# SCH_TEST_2022-02-16.net
KiCad netlist of a schematic drawn in EasyEDA
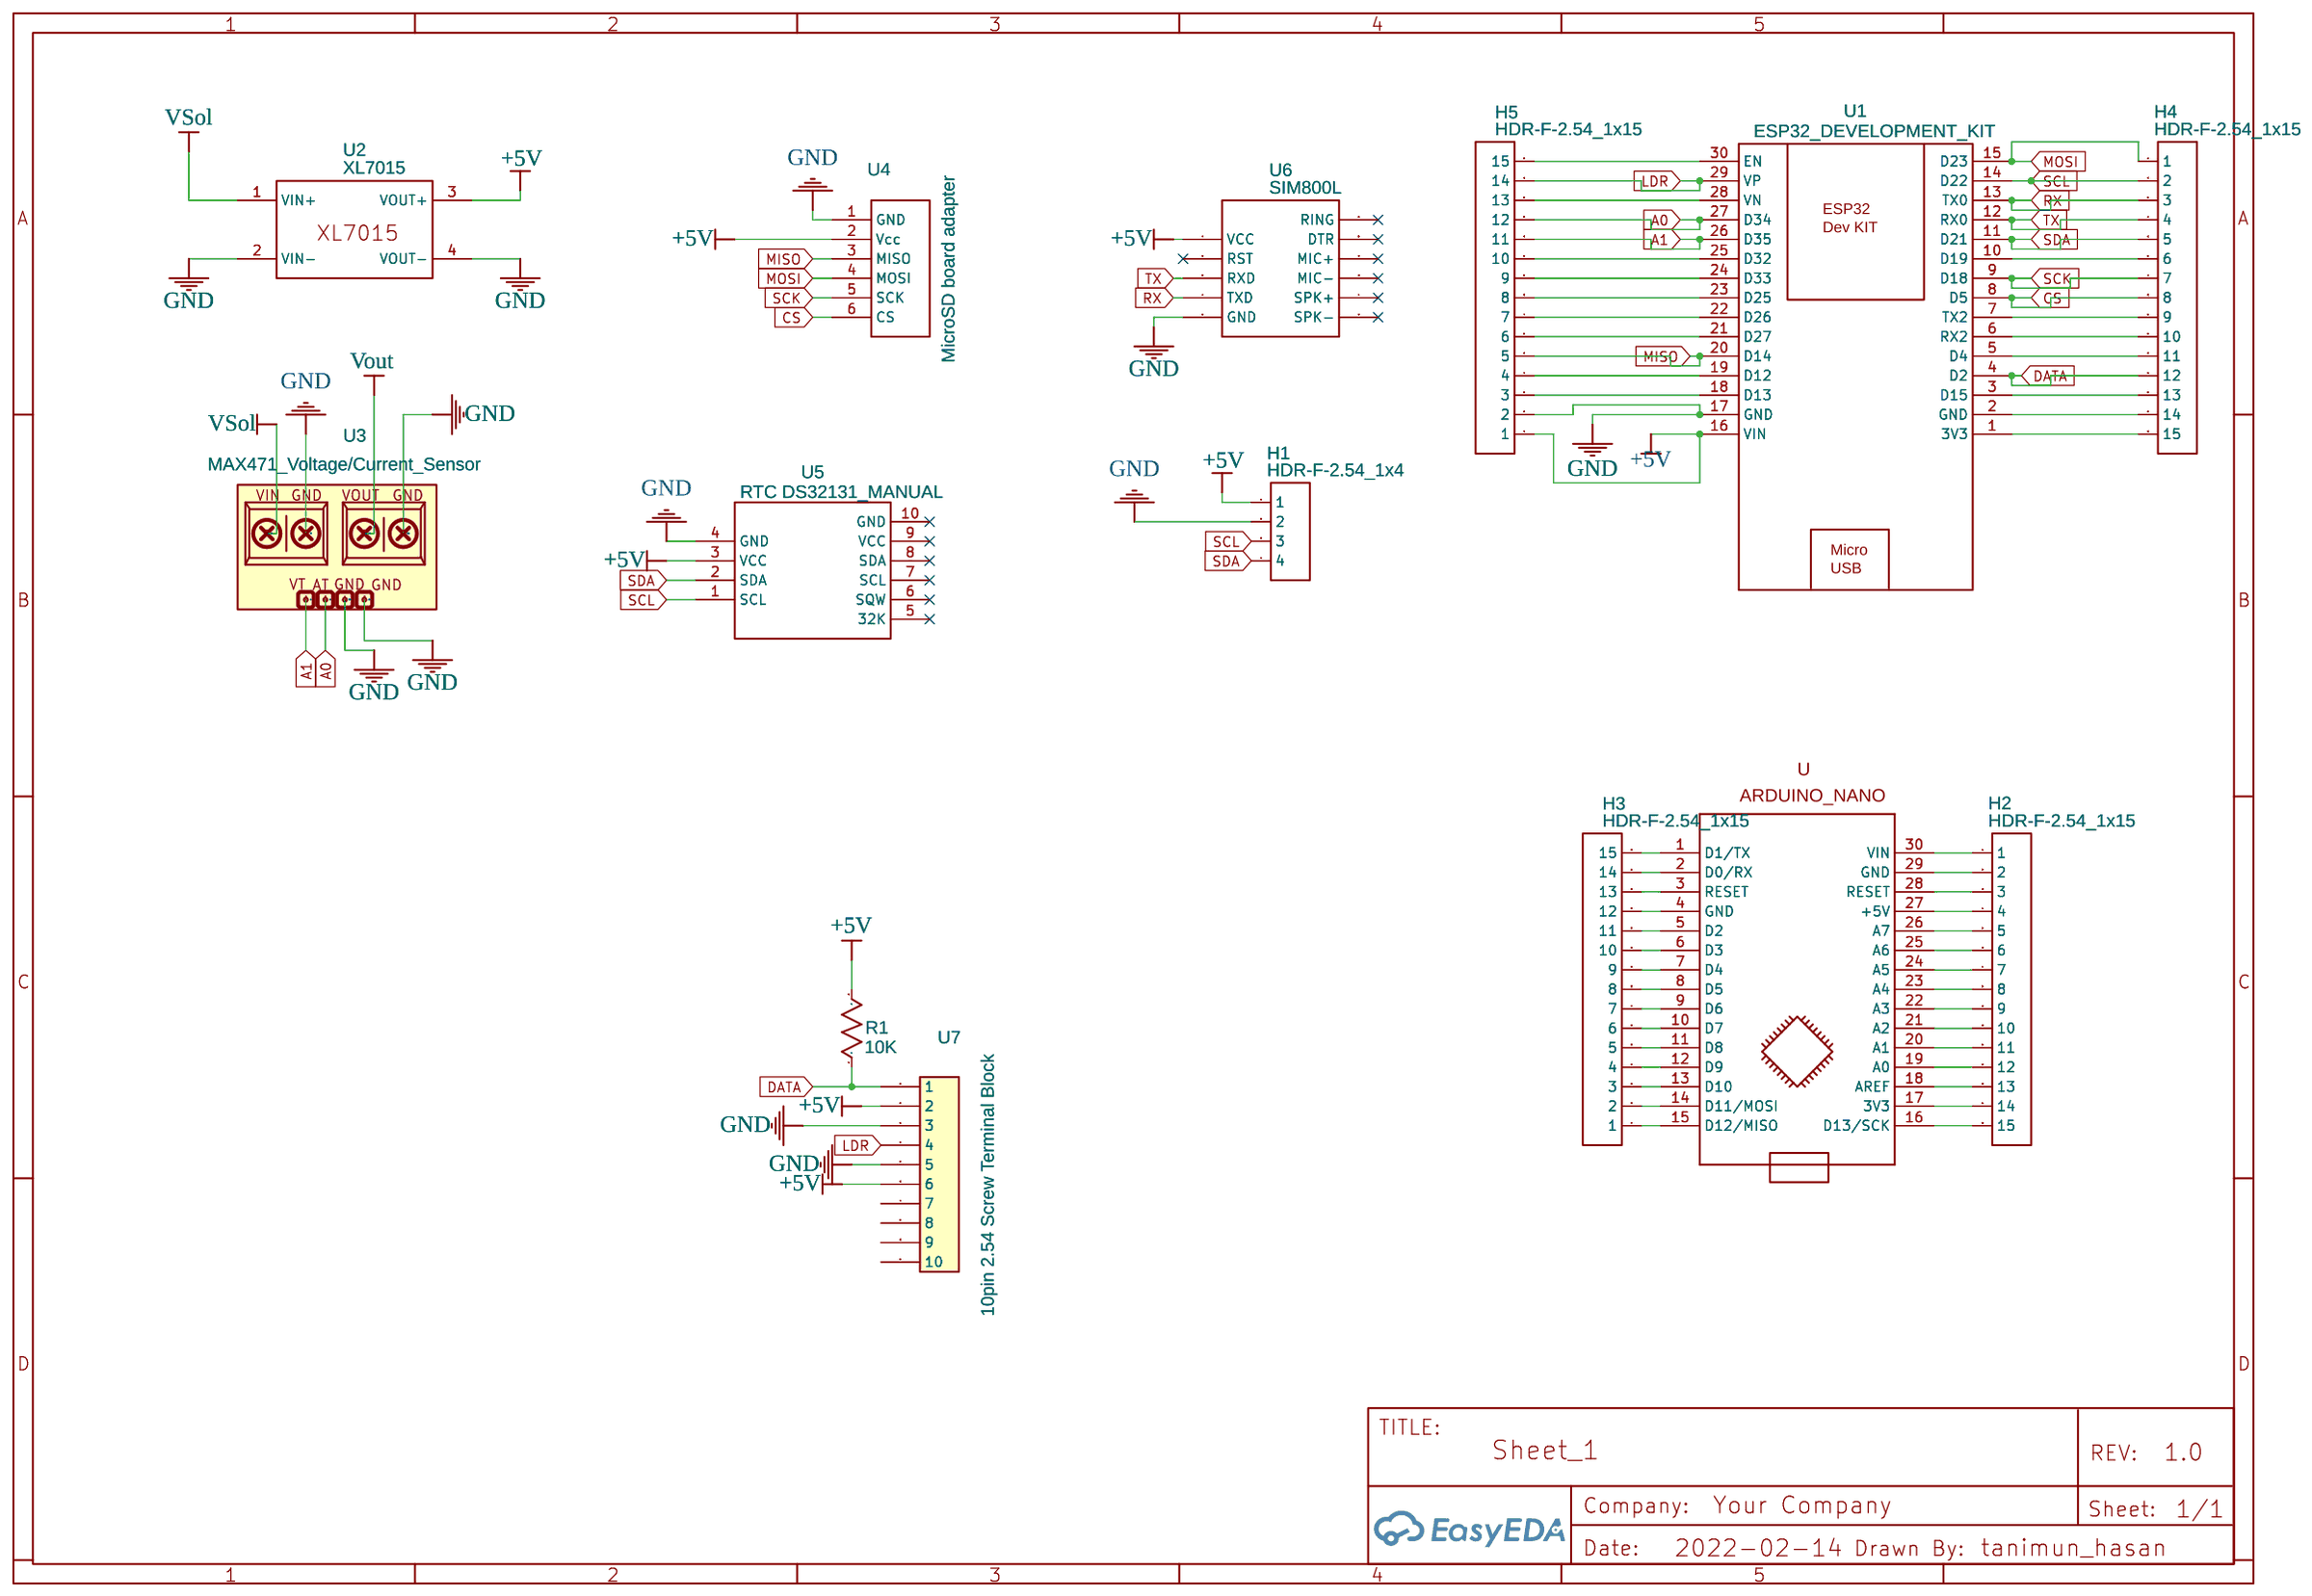
[diagram p0: schematic sheet]

(export (version "E")
  (design (tool "Eeschema 10.0.6"))
  (components
    (comp (ref "H1")
      (value "HDR-F-2.54_1x4")
      (fields (field (name "BOM_Supplier Part") "C225501"))
      (libsource (lib "") (part "HDR-F-2.54_1x4"))
    )
    (comp (ref "H2")
      (value "HDR-F-2.54_1x15")
      (fields (field (name "BOM_Supplier Part") "C124408"))
      (libsource (lib "") (part "HDR-F-2.54_1x15_1"))
    )
    (comp (ref "H3")
      (value "HDR-F-2.54_1x15")
      (fields (field (name "BOM_Supplier Part") "C124408"))
      (libsource (lib "") (part "HDR-F-2.54_1x15"))
    )
    (comp (ref "H4")
      (value "HDR-F-2.54_1x15")
      (fields (field (name "BOM_Supplier Part") "C124408"))
      (libsource (lib "") (part "HDR-F-2.54_1x15_1"))
    )
    (comp (ref "H5")
      (value "HDR-F-2.54_1x15")
      (fields (field (name "BOM_Supplier Part") "C124408"))
      (libsource (lib "") (part "HDR-F-2.54_1x15"))
    )
    (comp (ref "R1") (value "10K") (libsource (lib "") (part "R_AXIAL-0.4_US")))
    (comp (ref "U1")
      (value "ESP32_DEVELOPMENT_KIT")
      (fields (field (name "BOM_Manufacturer Part") "ESP32 Development KIT"))
      (libsource (lib "") (part "ESP32_DEVELOPMENT_KIT"))
    )
    (comp (ref "U2") (value "XL7015") (libsource (lib "") (part "XL7015")))
    (comp (ref "U3")
      (value "MAX471_Voltage/Current_Sensor")
      (libsource (lib "") (part "MAX471_Voltage/Current_Sensor"))
    )
    (comp (ref "U4") (value "MicroSD board adapter") (libsource (lib "") (part "MicroSD board adapter")))
    (comp (ref "U5") (value "RTC DS32131_MANUAL") (libsource (lib "") (part "RTC DS32131_MANUAL")))
    (comp (ref "U6") (value "SIM800L") (libsource (lib "") (part "SIM800L")))
    (comp (ref "U7")
      (value "10pin 2.54 Screw Terminal Block")
      (libsource (lib "") (part "10pin 2.54 Screw Terminal Block"))
    )
    (comp (ref "U8")
      (value "Arduino-NANO")
      (fields (field (name "BOM_Supplier Part") "undefined"))
      (libsource (lib "") (part "Arduino-NANO"))
    )
  )
  (nets
    (net (code "1") (name "+5V") (class "Default")
      (node (ref "H1") (pin "1") (pinfunction "1_1") (pintype "unspecified"))
      (node (ref "H5") (pin "1") (pinfunction "1_1") (pintype "unspecified"))
      (node (ref "R1") (pin "2") (pinfunction "2_2") (pintype "unspecified"))
      (node (ref "U1") (pin "16") (pinfunction "VIN_16") (pintype "unspecified"))
      (node (ref "U2") (pin "3") (pinfunction "VOUT+_3") (pintype "unspecified"))
      (node (ref "U4") (pin "2") (pinfunction "Vcc_2") (pintype "unspecified"))
      (node (ref "U5") (pin "3") (pinfunction "VCC_3") (pintype "unspecified"))
      (node (ref "U6") (pin "1") (pinfunction "VCC_1") (pintype "unspecified"))
      (node (ref "U7") (pin "2") (pinfunction "2_2") (pintype "input"))
      (node (ref "U7") (pin "6") (pinfunction "6_6") (pintype "input"))
    )
    (net (code "2") (name "A0") (class "Default")
      (node (ref "H5") (pin "12") (pinfunction "12_12") (pintype "unspecified"))
      (node (ref "U1") (pin "27") (pinfunction "D34_27") (pintype "unspecified"))
      (node (ref "U3") (pin "6") (pinfunction "AT_6") (pintype "unspecified"))
    )
    (net (code "3") (name "A1") (class "Default")
      (node (ref "H5") (pin "11") (pinfunction "11_11") (pintype "unspecified"))
      (node (ref "U1") (pin "26") (pinfunction "D35_26") (pintype "unspecified"))
      (node (ref "U3") (pin "5") (pinfunction "VT_5") (pintype "unspecified"))
    )
    (net (code "4") (name "CS") (class "Default")
      (node (ref "H4") (pin "8") (pinfunction "8_8") (pintype "unspecified"))
      (node (ref "U1") (pin "8") (pinfunction "D5_8") (pintype "unspecified"))
      (node (ref "U4") (pin "6") (pinfunction "CS_6") (pintype "unspecified"))
    )
    (net (code "5") (name "DATA") (class "Default")
      (node (ref "H4") (pin "12") (pinfunction "12_12") (pintype "unspecified"))
      (node (ref "R1") (pin "1") (pinfunction "1_1") (pintype "unspecified"))
      (node (ref "U1") (pin "4") (pinfunction "D2_4") (pintype "unspecified"))
      (node (ref "U7") (pin "1") (pinfunction "1_1") (pintype "input"))
    )
    (net (code "6") (name "GND") (class "Default")
      (node (ref "H1") (pin "2") (pinfunction "2_2") (pintype "unspecified"))
      (node (ref "H5") (pin "2") (pinfunction "2_2") (pintype "unspecified"))
      (node (ref "U1") (pin "17") (pinfunction "GND_17") (pintype "unspecified"))
      (node (ref "U2") (pin "2") (pinfunction "VIN-_2") (pintype "unspecified"))
      (node (ref "U2") (pin "4") (pinfunction "VOUT-_4") (pintype "unspecified"))
      (node (ref "U3") (pin "2") (pinfunction "GND_2") (pintype "unspecified"))
      (node (ref "U3") (pin "4") (pinfunction "GND_4") (pintype "unspecified"))
      (node (ref "U3") (pin "7") (pinfunction "GND_7") (pintype "unspecified"))
      (node (ref "U3") (pin "8") (pinfunction "GND_8") (pintype "unspecified"))
      (node (ref "U4") (pin "1") (pinfunction "GND_1") (pintype "unspecified"))
      (node (ref "U5") (pin "4") (pinfunction "GND_4") (pintype "unspecified"))
      (node (ref "U6") (pin "5") (pinfunction "GND_5") (pintype "unspecified"))
      (node (ref "U7") (pin "3") (pinfunction "3_3") (pintype "input"))
      (node (ref "U7") (pin "5") (pinfunction "5_5") (pintype "input"))
    )
    (net (code "7") (name "LDR") (class "Default")
      (node (ref "H5") (pin "14") (pinfunction "14_14") (pintype "unspecified"))
      (node (ref "U1") (pin "29") (pinfunction "VP_29") (pintype "unspecified"))
      (node (ref "U7") (pin "4") (pinfunction "4_4") (pintype "input"))
    )
    (net (code "8") (name "MISO") (class "Default")
      (node (ref "H5") (pin "5") (pinfunction "5_5") (pintype "unspecified"))
      (node (ref "U1") (pin "20") (pinfunction "D14_20") (pintype "unspecified"))
      (node (ref "U4") (pin "3") (pinfunction "MISO_3") (pintype "unspecified"))
    )
    (net (code "9") (name "MOSI") (class "Default")
      (node (ref "H4") (pin "1") (pinfunction "1_1") (pintype "unspecified"))
      (node (ref "U1") (pin "15") (pinfunction "D23_15") (pintype "unspecified"))
      (node (ref "U4") (pin "4") (pinfunction "MOSI_4") (pintype "unspecified"))
    )
    (net (code "10") (name "Net-(H2-Pad2)") (class "Default")
      (node (ref "H2") (pin "2") (pinfunction "2_2") (pintype "unspecified"))
      (node (ref "U8") (pin "29") (pinfunction "GND_29") (pintype "unspecified"))
    )
    (net (code "11") (name "Net-(H2-Pad3)") (class "Default")
      (node (ref "H2") (pin "3") (pinfunction "3_3") (pintype "unspecified"))
      (node (ref "U8") (pin "28") (pinfunction "RESET_28") (pintype "unspecified"))
    )
    (net (code "12") (name "Net-(H3-Pad12)") (class "Default")
      (node (ref "H3") (pin "12") (pinfunction "12_12") (pintype "unspecified"))
      (node (ref "U8") (pin "4") (pinfunction "GND_4") (pintype "unspecified"))
    )
    (net (code "13") (name "Net-(H3-Pad13)") (class "Default")
      (node (ref "H3") (pin "13") (pinfunction "13_13") (pintype "unspecified"))
      (node (ref "U8") (pin "3") (pinfunction "RESET_3") (pintype "unspecified"))
    )
    (net (code "14") (name "Net-(H4-Pad14)") (class "Default")
      (node (ref "H4") (pin "14") (pinfunction "14_14") (pintype "unspecified"))
      (node (ref "U1") (pin "2") (pinfunction "GND_2") (pintype "unspecified"))
    )
    (net (code "15") (name "Net-(U1-3V3)") (class "Default")
      (node (ref "H4") (pin "15") (pinfunction "15_15") (pintype "unspecified"))
      (node (ref "U1") (pin "1") (pinfunction "3V3_1") (pintype "unspecified"))
    )
    (net (code "16") (name "Net-(U1-D4)") (class "Default")
      (node (ref "H4") (pin "11") (pinfunction "11_11") (pintype "unspecified"))
      (node (ref "U1") (pin "5") (pinfunction "D4_5") (pintype "unspecified"))
    )
    (net (code "17") (name "Net-(U1-D12)") (class "Default")
      (node (ref "H5") (pin "4") (pinfunction "4_4") (pintype "unspecified"))
      (node (ref "U1") (pin "19") (pinfunction "D12_19") (pintype "unspecified"))
    )
    (net (code "18") (name "Net-(U1-D13)") (class "Default")
      (node (ref "H5") (pin "3") (pinfunction "3_3") (pintype "unspecified"))
      (node (ref "U1") (pin "18") (pinfunction "D13_18") (pintype "unspecified"))
    )
    (net (code "19") (name "Net-(U1-D15)") (class "Default")
      (node (ref "H4") (pin "13") (pinfunction "13_13") (pintype "unspecified"))
      (node (ref "U1") (pin "3") (pinfunction "D15_3") (pintype "unspecified"))
    )
    (net (code "20") (name "Net-(U1-D19)") (class "Default")
      (node (ref "H4") (pin "6") (pinfunction "6_6") (pintype "unspecified"))
      (node (ref "U1") (pin "10") (pinfunction "D19_10") (pintype "unspecified"))
    )
    (net (code "21") (name "Net-(U1-D25)") (class "Default")
      (node (ref "H5") (pin "8") (pinfunction "8_8") (pintype "unspecified"))
      (node (ref "U1") (pin "23") (pinfunction "D25_23") (pintype "unspecified"))
    )
    (net (code "22") (name "Net-(U1-D26)") (class "Default")
      (node (ref "H5") (pin "7") (pinfunction "7_7") (pintype "unspecified"))
      (node (ref "U1") (pin "22") (pinfunction "D26_22") (pintype "unspecified"))
    )
    (net (code "23") (name "Net-(U1-D27)") (class "Default")
      (node (ref "H5") (pin "6") (pinfunction "6_6") (pintype "unspecified"))
      (node (ref "U1") (pin "21") (pinfunction "D27_21") (pintype "unspecified"))
    )
    (net (code "24") (name "Net-(U1-D32)") (class "Default")
      (node (ref "H5") (pin "10") (pinfunction "10_10") (pintype "unspecified"))
      (node (ref "U1") (pin "25") (pinfunction "D32_25") (pintype "unspecified"))
    )
    (net (code "25") (name "Net-(U1-D33)") (class "Default")
      (node (ref "H5") (pin "9") (pinfunction "9_9") (pintype "unspecified"))
      (node (ref "U1") (pin "24") (pinfunction "D33_24") (pintype "unspecified"))
    )
    (net (code "26") (name "Net-(U1-EN)") (class "Default")
      (node (ref "H5") (pin "15") (pinfunction "15_15") (pintype "unspecified"))
      (node (ref "U1") (pin "30") (pinfunction "EN_30") (pintype "unspecified"))
    )
    (net (code "27") (name "Net-(U1-RX2)") (class "Default")
      (node (ref "H4") (pin "10") (pinfunction "10_10") (pintype "unspecified"))
      (node (ref "U1") (pin "6") (pinfunction "RX2_6") (pintype "unspecified"))
    )
    (net (code "28") (name "Net-(U1-TX2)") (class "Default")
      (node (ref "H4") (pin "9") (pinfunction "9_9") (pintype "unspecified"))
      (node (ref "U1") (pin "7") (pinfunction "TX2_7") (pintype "unspecified"))
    )
    (net (code "29") (name "Net-(U1-VN)") (class "Default")
      (node (ref "H5") (pin "13") (pinfunction "13_13") (pintype "unspecified"))
      (node (ref "U1") (pin "28") (pinfunction "VN_28") (pintype "unspecified"))
    )
    (net (code "30") (name "Net-(U8-+5V)") (class "Default")
      (node (ref "H2") (pin "4") (pinfunction "4_4") (pintype "unspecified"))
      (node (ref "U8") (pin "27") (pinfunction "+5V_27") (pintype "unspecified"))
    )
    (net (code "31") (name "Net-(U8-3V3)") (class "Default")
      (node (ref "H2") (pin "14") (pinfunction "14_14") (pintype "unspecified"))
      (node (ref "U8") (pin "17") (pinfunction "3V3_17") (pintype "unspecified"))
    )
    (net (code "32") (name "Net-(U8-A0)") (class "Default")
      (node (ref "H2") (pin "12") (pinfunction "12_12") (pintype "unspecified"))
      (node (ref "U8") (pin "19") (pinfunction "A0_19") (pintype "unspecified"))
    )
    (net (code "33") (name "Net-(U8-A1)") (class "Default")
      (node (ref "H2") (pin "11") (pinfunction "11_11") (pintype "unspecified"))
      (node (ref "U8") (pin "20") (pinfunction "A1_20") (pintype "unspecified"))
    )
    (net (code "34") (name "Net-(U8-A2)") (class "Default")
      (node (ref "H2") (pin "10") (pinfunction "10_10") (pintype "unspecified"))
      (node (ref "U8") (pin "21") (pinfunction "A2_21") (pintype "unspecified"))
    )
    (net (code "35") (name "Net-(U8-A3)") (class "Default")
      (node (ref "H2") (pin "9") (pinfunction "9_9") (pintype "unspecified"))
      (node (ref "U8") (pin "22") (pinfunction "A3_22") (pintype "unspecified"))
    )
    (net (code "36") (name "Net-(U8-A4)") (class "Default")
      (node (ref "H2") (pin "8") (pinfunction "8_8") (pintype "unspecified"))
      (node (ref "U8") (pin "23") (pinfunction "A4_23") (pintype "unspecified"))
    )
    (net (code "37") (name "Net-(U8-A5)") (class "Default")
      (node (ref "H2") (pin "7") (pinfunction "7_7") (pintype "unspecified"))
      (node (ref "U8") (pin "24") (pinfunction "A5_24") (pintype "unspecified"))
    )
    (net (code "38") (name "Net-(U8-A6)") (class "Default")
      (node (ref "H2") (pin "6") (pinfunction "6_6") (pintype "unspecified"))
      (node (ref "U8") (pin "25") (pinfunction "A6_25") (pintype "unspecified"))
    )
    (net (code "39") (name "Net-(U8-A7)") (class "Default")
      (node (ref "H2") (pin "5") (pinfunction "5_5") (pintype "unspecified"))
      (node (ref "U8") (pin "26") (pinfunction "A7_26") (pintype "unspecified"))
    )
    (net (code "40") (name "Net-(U8-AREF)") (class "Default")
      (node (ref "H2") (pin "13") (pinfunction "13_13") (pintype "unspecified"))
      (node (ref "U8") (pin "18") (pinfunction "AREF_18") (pintype "unspecified"))
    )
    (net (code "41") (name "Net-(U8-D0{slash}RX)") (class "Default")
      (node (ref "H3") (pin "14") (pinfunction "14_14") (pintype "unspecified"))
      (node (ref "U8") (pin "2") (pinfunction "D0/RX_2") (pintype "unspecified"))
    )
    (net (code "42") (name "Net-(U8-D1{slash}TX)") (class "Default")
      (node (ref "H3") (pin "15") (pinfunction "15_15") (pintype "unspecified"))
      (node (ref "U8") (pin "1") (pinfunction "D1/TX_1") (pintype "unspecified"))
    )
    (net (code "43") (name "Net-(U8-D2)") (class "Default")
      (node (ref "H3") (pin "11") (pinfunction "11_11") (pintype "unspecified"))
      (node (ref "U8") (pin "5") (pinfunction "D2_5") (pintype "unspecified"))
    )
    (net (code "44") (name "Net-(U8-D3)") (class "Default")
      (node (ref "H3") (pin "10") (pinfunction "10_10") (pintype "unspecified"))
      (node (ref "U8") (pin "6") (pinfunction "D3_6") (pintype "unspecified"))
    )
    (net (code "45") (name "Net-(U8-D4)") (class "Default")
      (node (ref "H3") (pin "9") (pinfunction "9_9") (pintype "unspecified"))
      (node (ref "U8") (pin "7") (pinfunction "D4_7") (pintype "unspecified"))
    )
    (net (code "46") (name "Net-(U8-D5)") (class "Default")
      (node (ref "H3") (pin "8") (pinfunction "8_8") (pintype "unspecified"))
      (node (ref "U8") (pin "8") (pinfunction "D5_8") (pintype "unspecified"))
    )
    (net (code "47") (name "Net-(U8-D6)") (class "Default")
      (node (ref "H3") (pin "7") (pinfunction "7_7") (pintype "unspecified"))
      (node (ref "U8") (pin "9") (pinfunction "D6_9") (pintype "unspecified"))
    )
    (net (code "48") (name "Net-(U8-D7)") (class "Default")
      (node (ref "H3") (pin "6") (pinfunction "6_6") (pintype "unspecified"))
      (node (ref "U8") (pin "10") (pinfunction "D7_10") (pintype "unspecified"))
    )
    (net (code "49") (name "Net-(U8-D8)") (class "Default")
      (node (ref "H3") (pin "5") (pinfunction "5_5") (pintype "unspecified"))
      (node (ref "U8") (pin "11") (pinfunction "D8_11") (pintype "unspecified"))
    )
    (net (code "50") (name "Net-(U8-D9)") (class "Default")
      (node (ref "H3") (pin "4") (pinfunction "4_4") (pintype "unspecified"))
      (node (ref "U8") (pin "12") (pinfunction "D9_12") (pintype "unspecified"))
    )
    (net (code "51") (name "Net-(U8-D10)") (class "Default")
      (node (ref "H3") (pin "3") (pinfunction "3_3") (pintype "unspecified"))
      (node (ref "U8") (pin "13") (pinfunction "D10_13") (pintype "unspecified"))
    )
    (net (code "52") (name "Net-(U8-D11{slash}MOSI)") (class "Default")
      (node (ref "H3") (pin "2") (pinfunction "2_2") (pintype "unspecified"))
      (node (ref "U8") (pin "14") (pinfunction "D11/MOSI_14") (pintype "unspecified"))
    )
    (net (code "53") (name "Net-(U8-D12{slash}MISO)") (class "Default")
      (node (ref "H3") (pin "1") (pinfunction "1_1") (pintype "unspecified"))
      (node (ref "U8") (pin "15") (pinfunction "D12/MISO_15") (pintype "unspecified"))
    )
    (net (code "54") (name "Net-(U8-D13{slash}SCK)") (class "Default")
      (node (ref "H2") (pin "15") (pinfunction "15_15") (pintype "unspecified"))
      (node (ref "U8") (pin "16") (pinfunction "D13/SCK_16") (pintype "unspecified"))
    )
    (net (code "55") (name "Net-(U8-VIN)") (class "Default")
      (node (ref "H2") (pin "1") (pinfunction "1_1") (pintype "unspecified"))
      (node (ref "U8") (pin "30") (pinfunction "VIN_30") (pintype "unspecified"))
    )
    (net (code "56") (name "RX") (class "Default")
      (node (ref "H4") (pin "3") (pinfunction "3_3") (pintype "unspecified"))
      (node (ref "U1") (pin "13") (pinfunction "TX0_13") (pintype "unspecified"))
      (node (ref "U6") (pin "4") (pinfunction "TXD_4") (pintype "unspecified"))
    )
    (net (code "57") (name "SCK") (class "Default")
      (node (ref "H4") (pin "7") (pinfunction "7_7") (pintype "unspecified"))
      (node (ref "U1") (pin "9") (pinfunction "D18_9") (pintype "unspecified"))
      (node (ref "U4") (pin "5") (pinfunction "SCK_5") (pintype "unspecified"))
    )
    (net (code "58") (name "SCL") (class "Default")
      (node (ref "H1") (pin "3") (pinfunction "3_3") (pintype "unspecified"))
      (node (ref "H4") (pin "2") (pinfunction "2_2") (pintype "unspecified"))
      (node (ref "U1") (pin "14") (pinfunction "D22_14") (pintype "unspecified"))
      (node (ref "U5") (pin "1") (pinfunction "SCL_1") (pintype "unspecified"))
    )
    (net (code "59") (name "SDA") (class "Default")
      (node (ref "H1") (pin "4") (pinfunction "4_4") (pintype "unspecified"))
      (node (ref "H4") (pin "5") (pinfunction "5_5") (pintype "unspecified"))
      (node (ref "U1") (pin "11") (pinfunction "D21_11") (pintype "unspecified"))
      (node (ref "U5") (pin "2") (pinfunction "SDA_2") (pintype "unspecified"))
    )
    (net (code "60") (name "TX") (class "Default")
      (node (ref "H4") (pin "4") (pinfunction "4_4") (pintype "unspecified"))
      (node (ref "U1") (pin "12") (pinfunction "RX0_12") (pintype "unspecified"))
      (node (ref "U6") (pin "3") (pinfunction "RXD_3") (pintype "unspecified"))
    )
    (net (code "61") (name "VSol") (class "Default")
      (node (ref "U2") (pin "1") (pinfunction "VIN+_1") (pintype "unspecified"))
      (node (ref "U3") (pin "1") (pinfunction "VIN_1") (pintype "unspecified"))
    )
    (net (code "62") (name "Vout") (class "Default")
      (node (ref "U3") (pin "3") (pinfunction "VOUT_3") (pintype "unspecified"))
    )
    (net (code "63") (name "unconnected-(U5-32K-Pad5)") (class "Default")
      (node (ref "U5") (pin "5") (pinfunction "32K_5") (pintype "unspecified+no_connect"))
    )
    (net (code "64") (name "unconnected-(U5-GND-Pad10)") (class "Default")
      (node (ref "U5") (pin "10") (pinfunction "GND_10") (pintype "unspecified+no_connect"))
    )
    (net (code "65") (name "unconnected-(U5-SCL-Pad7)") (class "Default")
      (node (ref "U5") (pin "7") (pinfunction "SCL_7") (pintype "unspecified+no_connect"))
    )
    (net (code "66") (name "unconnected-(U5-SDA-Pad8)") (class "Default")
      (node (ref "U5") (pin "8") (pinfunction "SDA_8") (pintype "unspecified+no_connect"))
    )
    (net (code "67") (name "unconnected-(U5-SQW-Pad6)") (class "Default")
      (node (ref "U5") (pin "6") (pinfunction "SQW_6") (pintype "unspecified+no_connect"))
    )
    (net (code "68") (name "unconnected-(U5-VCC-Pad9)") (class "Default")
      (node (ref "U5") (pin "9") (pinfunction "VCC_9") (pintype "unspecified+no_connect"))
    )
    (net (code "69") (name "unconnected-(U6-DTR-Pad10)") (class "Default")
      (node (ref "U6") (pin "10") (pinfunction "DTR_10") (pintype "unspecified+no_connect"))
    )
    (net (code "70") (name "unconnected-(U6-MIC+-Pad9)") (class "Default")
      (node (ref "U6") (pin "9") (pinfunction "MIC+_9") (pintype "unspecified+no_connect"))
    )
    (net (code "71") (name "unconnected-(U6-MIC--Pad8)") (class "Default")
      (node (ref "U6") (pin "8") (pinfunction "MIC-_8") (pintype "unspecified+no_connect"))
    )
    (net (code "72") (name "unconnected-(U6-RING-Pad11)") (class "Default")
      (node (ref "U6") (pin "11") (pinfunction "RING_11") (pintype "unspecified+no_connect"))
    )
    (net (code "73") (name "unconnected-(U6-RST-Pad2)") (class "Default")
      (node (ref "U6") (pin "2") (pinfunction "RST_2") (pintype "unspecified+no_connect"))
    )
    (net (code "74") (name "unconnected-(U6-SPK+-Pad7)") (class "Default")
      (node (ref "U6") (pin "7") (pinfunction "SPK+_7") (pintype "unspecified+no_connect"))
    )
    (net (code "75") (name "unconnected-(U6-SPK--Pad6)") (class "Default")
      (node (ref "U6") (pin "6") (pinfunction "SPK-_6") (pintype "unspecified+no_connect"))
    )
    (net (code "76") (name "unconnected-(U7-Pad7)") (class "Default")
      (node (ref "U7") (pin "7") (pinfunction "7_7") (pintype "input"))
    )
    (net (code "77") (name "unconnected-(U7-Pad8)") (class "Default")
      (node (ref "U7") (pin "8") (pinfunction "8_8") (pintype "input"))
    )
    (net (code "78") (name "unconnected-(U7-Pad9)") (class "Default")
      (node (ref "U7") (pin "9") (pinfunction "9_9") (pintype "input"))
    )
    (net (code "79") (name "unconnected-(U7-Pad10)") (class "Default")
      (node (ref "U7") (pin "10") (pinfunction "10_10") (pintype "input"))
    )
  )
)
